# 23005_2.net
KiCad netlist of a schematic drawn in Altium Designer
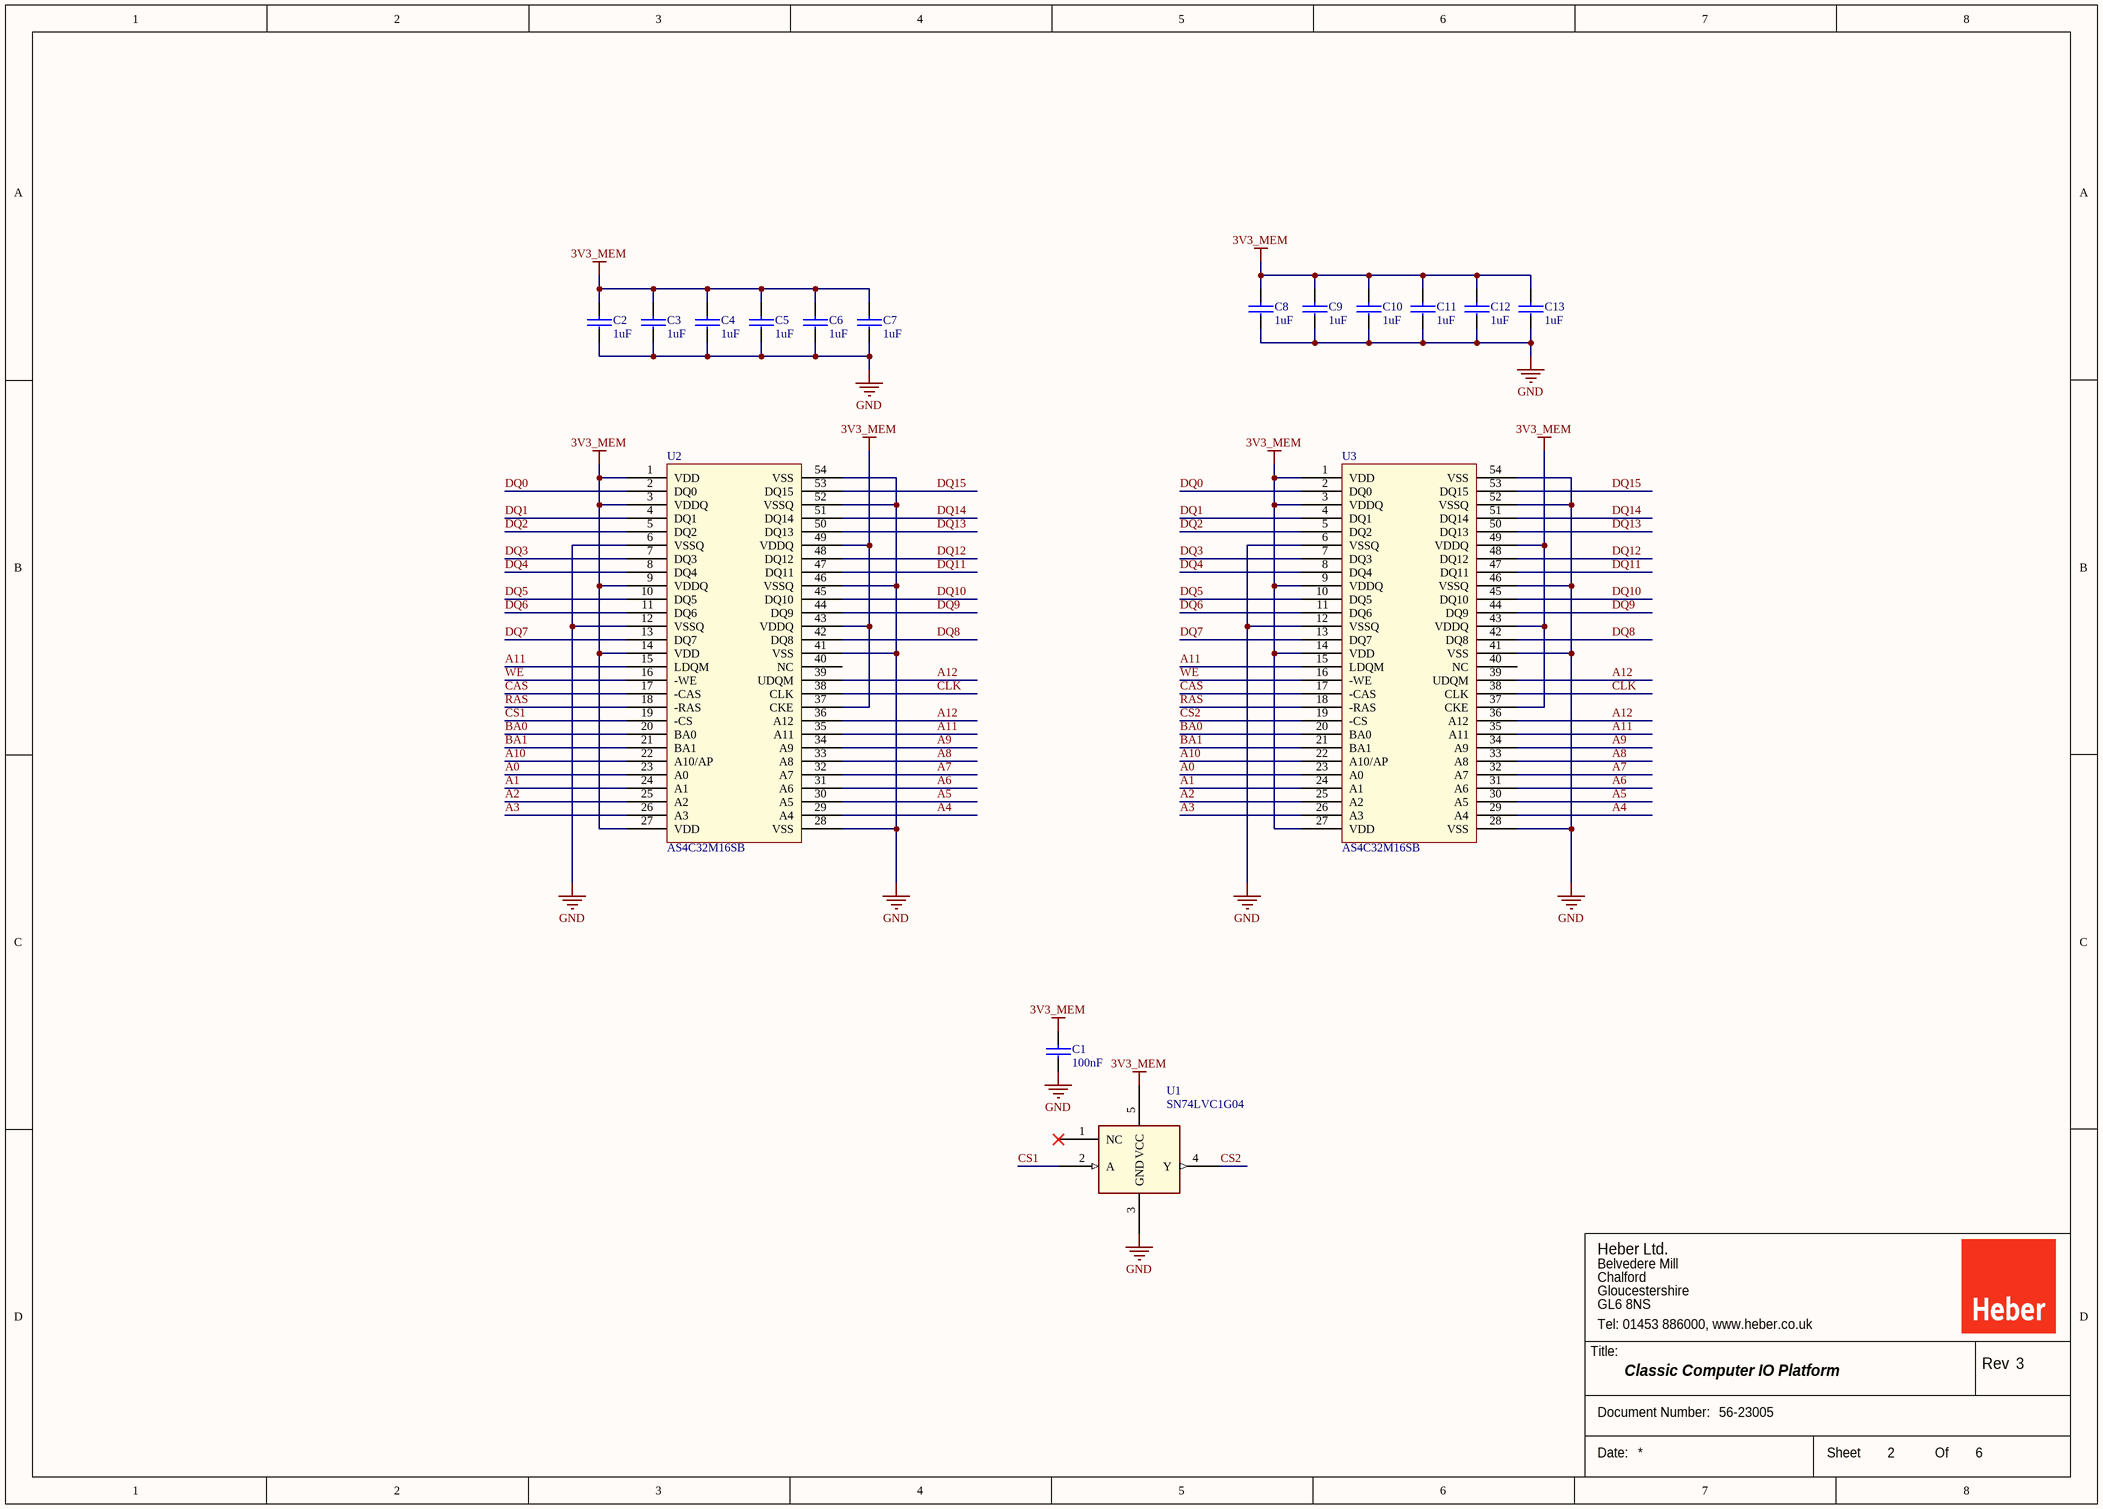
[diagram p0: 23005_2.SchDoc]

(export (version "E")
  (design (tool "Eeschema 10.0.6"))
  (components
    (comp (ref "C1") (value "100nF") (footprint "SM0603") (libsource (lib "LIBRARY1_Library") (part "C")))
    (comp (ref "C2") (value "1uF") (footprint "SM0603") (libsource (lib "LIBRARY1_Library") (part "C")))
    (comp (ref "C3") (value "1uF") (footprint "SM0603") (libsource (lib "LIBRARY1_Library") (part "C")))
    (comp (ref "C4") (value "1uF") (footprint "SM0603") (libsource (lib "LIBRARY1_Library") (part "C")))
    (comp (ref "C5") (value "1uF") (footprint "SM0603") (libsource (lib "LIBRARY1_Library") (part "C")))
    (comp (ref "C6") (value "1uF") (footprint "SM0603") (libsource (lib "LIBRARY1_Library") (part "C")))
    (comp (ref "C7") (value "1uF") (footprint "SM0603") (libsource (lib "LIBRARY1_Library") (part "C")))
    (comp (ref "C8") (value "1uF") (footprint "SM0603") (libsource (lib "LIBRARY1_Library") (part "C")))
    (comp (ref "C9") (value "1uF") (footprint "SM0603") (libsource (lib "LIBRARY1_Library") (part "C")))
    (comp (ref "C10") (value "1uF") (footprint "SM0603") (libsource (lib "LIBRARY1_Library") (part "C")))
    (comp (ref "C11") (value "1uF") (footprint "SM0603") (libsource (lib "LIBRARY1_Library") (part "C")))
    (comp (ref "C12") (value "1uF") (footprint "SM0603") (libsource (lib "LIBRARY1_Library") (part "C")))
    (comp (ref "C13") (value "1uF") (footprint "SM0603") (libsource (lib "LIBRARY1_Library") (part "C")))
    (comp (ref "U1")
      (value "SN74LVC1G04")
      (footprint "SOT23-5")
      (libsource (lib "LIBRARY1_Library") (part "SN74LVC1G07"))
    )
    (comp (ref "U2")
      (value "AS4C32M16SB")
      (footprint "TSOP54/080")
      (libsource (lib "23005") (part "AS4C32M16SB"))
    )
    (comp (ref "U3")
      (value "AS4C32M16SB")
      (footprint "TSOP54/080")
      (libsource (lib "23005") (part "AS4C32M16SB"))
    )
  )
  (nets
    (net (code "1") (name "/A0") (class "Default")
      (node (ref "U2") (pin "23") (pinfunction "A0_23") (pintype "passive"))
      (node (ref "U3") (pin "23") (pinfunction "A0_23") (pintype "passive"))
    )
    (net (code "2") (name "/A1") (class "Default")
      (node (ref "U2") (pin "24") (pinfunction "A1_24") (pintype "passive"))
      (node (ref "U3") (pin "24") (pinfunction "A1_24") (pintype "passive"))
    )
    (net (code "3") (name "/A2") (class "Default")
      (node (ref "U2") (pin "25") (pinfunction "A2_25") (pintype "passive"))
      (node (ref "U3") (pin "25") (pinfunction "A2_25") (pintype "passive"))
    )
    (net (code "4") (name "/A3") (class "Default")
      (node (ref "U2") (pin "26") (pinfunction "A3_26") (pintype "passive"))
      (node (ref "U3") (pin "26") (pinfunction "A3_26") (pintype "passive"))
    )
    (net (code "5") (name "/A4") (class "Default")
      (node (ref "U2") (pin "29") (pinfunction "A4_29") (pintype "passive"))
      (node (ref "U3") (pin "29") (pinfunction "A4_29") (pintype "passive"))
    )
    (net (code "6") (name "/A5") (class "Default")
      (node (ref "U2") (pin "30") (pinfunction "A5_30") (pintype "passive"))
      (node (ref "U3") (pin "30") (pinfunction "A5_30") (pintype "passive"))
    )
    (net (code "7") (name "/A6") (class "Default")
      (node (ref "U2") (pin "31") (pinfunction "A6_31") (pintype "passive"))
      (node (ref "U3") (pin "31") (pinfunction "A6_31") (pintype "passive"))
    )
    (net (code "8") (name "/A7") (class "Default")
      (node (ref "U2") (pin "32") (pinfunction "A7_32") (pintype "passive"))
      (node (ref "U3") (pin "32") (pinfunction "A7_32") (pintype "passive"))
    )
    (net (code "9") (name "/A8") (class "Default")
      (node (ref "U2") (pin "33") (pinfunction "A8_33") (pintype "passive"))
      (node (ref "U3") (pin "33") (pinfunction "A8_33") (pintype "passive"))
    )
    (net (code "10") (name "/A9") (class "Default")
      (node (ref "U2") (pin "34") (pinfunction "A9_34") (pintype "passive"))
      (node (ref "U3") (pin "34") (pinfunction "A9_34") (pintype "passive"))
    )
    (net (code "11") (name "/A10") (class "Default")
      (node (ref "U2") (pin "22") (pinfunction "A10/AP_22") (pintype "passive"))
      (node (ref "U3") (pin "22") (pinfunction "A10/AP_22") (pintype "passive"))
    )
    (net (code "12") (name "/A11") (class "Default")
      (node (ref "U2") (pin "15") (pinfunction "LDQM_15") (pintype "passive"))
      (node (ref "U2") (pin "35") (pinfunction "A11_35") (pintype "passive"))
      (node (ref "U3") (pin "15") (pinfunction "LDQM_15") (pintype "passive"))
      (node (ref "U3") (pin "35") (pinfunction "A11_35") (pintype "passive"))
    )
    (net (code "13") (name "/A12") (class "Default")
      (node (ref "U2") (pin "36") (pinfunction "A12_36") (pintype "passive"))
      (node (ref "U2") (pin "39") (pinfunction "UDQM_39") (pintype "passive"))
      (node (ref "U3") (pin "36") (pinfunction "A12_36") (pintype "passive"))
      (node (ref "U3") (pin "39") (pinfunction "UDQM_39") (pintype "passive"))
    )
    (net (code "14") (name "/BA0") (class "Default")
      (node (ref "U2") (pin "20") (pinfunction "BA0_20") (pintype "passive"))
      (node (ref "U3") (pin "20") (pinfunction "BA0_20") (pintype "passive"))
    )
    (net (code "15") (name "/BA1") (class "Default")
      (node (ref "U2") (pin "21") (pinfunction "BA1_21") (pintype "passive"))
      (node (ref "U3") (pin "21") (pinfunction "BA1_21") (pintype "passive"))
    )
    (net (code "16") (name "/CAS") (class "Default")
      (node (ref "U2") (pin "17") (pinfunction "-CAS_17") (pintype "passive"))
      (node (ref "U3") (pin "17") (pinfunction "-CAS_17") (pintype "passive"))
    )
    (net (code "17") (name "/CLK") (class "Default")
      (node (ref "U2") (pin "38") (pinfunction "CLK_38") (pintype "passive"))
      (node (ref "U3") (pin "38") (pinfunction "CLK_38") (pintype "passive"))
    )
    (net (code "18") (name "/CS1") (class "Default")
      (node (ref "U1") (pin "2") (pinfunction "A_2") (pintype "input"))
      (node (ref "U2") (pin "19") (pinfunction "-CS_19") (pintype "passive"))
    )
    (net (code "19") (name "/CS2") (class "Default")
      (node (ref "U1") (pin "4") (pinfunction "Y_4") (pintype "output"))
      (node (ref "U3") (pin "19") (pinfunction "-CS_19") (pintype "passive"))
    )
    (net (code "20") (name "/DQ0") (class "Default")
      (node (ref "U2") (pin "2") (pinfunction "DQ0_2") (pintype "passive"))
      (node (ref "U3") (pin "2") (pinfunction "DQ0_2") (pintype "passive"))
    )
    (net (code "21") (name "/DQ1") (class "Default")
      (node (ref "U2") (pin "4") (pinfunction "DQ1_4") (pintype "passive"))
      (node (ref "U3") (pin "4") (pinfunction "DQ1_4") (pintype "passive"))
    )
    (net (code "22") (name "/DQ2") (class "Default")
      (node (ref "U2") (pin "5") (pinfunction "DQ2_5") (pintype "passive"))
      (node (ref "U3") (pin "5") (pinfunction "DQ2_5") (pintype "passive"))
    )
    (net (code "23") (name "/DQ3") (class "Default")
      (node (ref "U2") (pin "7") (pinfunction "DQ3_7") (pintype "passive"))
      (node (ref "U3") (pin "7") (pinfunction "DQ3_7") (pintype "passive"))
    )
    (net (code "24") (name "/DQ4") (class "Default")
      (node (ref "U2") (pin "8") (pinfunction "DQ4_8") (pintype "passive"))
      (node (ref "U3") (pin "8") (pinfunction "DQ4_8") (pintype "passive"))
    )
    (net (code "25") (name "/DQ5") (class "Default")
      (node (ref "U2") (pin "10") (pinfunction "DQ5_10") (pintype "passive"))
      (node (ref "U3") (pin "10") (pinfunction "DQ5_10") (pintype "passive"))
    )
    (net (code "26") (name "/DQ6") (class "Default")
      (node (ref "U2") (pin "11") (pinfunction "DQ6_11") (pintype "passive"))
      (node (ref "U3") (pin "11") (pinfunction "DQ6_11") (pintype "passive"))
    )
    (net (code "27") (name "/DQ7") (class "Default")
      (node (ref "U2") (pin "13") (pinfunction "DQ7_13") (pintype "passive"))
      (node (ref "U3") (pin "13") (pinfunction "DQ7_13") (pintype "passive"))
    )
    (net (code "28") (name "/DQ8") (class "Default")
      (node (ref "U2") (pin "42") (pinfunction "DQ8_42") (pintype "passive"))
      (node (ref "U3") (pin "42") (pinfunction "DQ8_42") (pintype "passive"))
    )
    (net (code "29") (name "/DQ9") (class "Default")
      (node (ref "U2") (pin "44") (pinfunction "DQ9_44") (pintype "passive"))
      (node (ref "U3") (pin "44") (pinfunction "DQ9_44") (pintype "passive"))
    )
    (net (code "30") (name "/DQ10") (class "Default")
      (node (ref "U2") (pin "45") (pinfunction "DQ10_45") (pintype "passive"))
      (node (ref "U3") (pin "45") (pinfunction "DQ10_45") (pintype "passive"))
    )
    (net (code "31") (name "/DQ11") (class "Default")
      (node (ref "U2") (pin "47") (pinfunction "DQ11_47") (pintype "passive"))
      (node (ref "U3") (pin "47") (pinfunction "DQ11_47") (pintype "passive"))
    )
    (net (code "32") (name "/DQ12") (class "Default")
      (node (ref "U2") (pin "48") (pinfunction "DQ12_48") (pintype "passive"))
      (node (ref "U3") (pin "48") (pinfunction "DQ12_48") (pintype "passive"))
    )
    (net (code "33") (name "/DQ13") (class "Default")
      (node (ref "U2") (pin "50") (pinfunction "DQ13_50") (pintype "passive"))
      (node (ref "U3") (pin "50") (pinfunction "DQ13_50") (pintype "passive"))
    )
    (net (code "34") (name "/DQ14") (class "Default")
      (node (ref "U2") (pin "51") (pinfunction "DQ14_51") (pintype "passive"))
      (node (ref "U3") (pin "51") (pinfunction "DQ14_51") (pintype "passive"))
    )
    (net (code "35") (name "/DQ15") (class "Default")
      (node (ref "U2") (pin "53") (pinfunction "DQ15_53") (pintype "passive"))
      (node (ref "U3") (pin "53") (pinfunction "DQ15_53") (pintype "passive"))
    )
    (net (code "36") (name "/RAS") (class "Default")
      (node (ref "U2") (pin "18") (pinfunction "-RAS_18") (pintype "passive"))
      (node (ref "U3") (pin "18") (pinfunction "-RAS_18") (pintype "passive"))
    )
    (net (code "37") (name "/WE") (class "Default")
      (node (ref "U2") (pin "16") (pinfunction "-WE_16") (pintype "passive"))
      (node (ref "U3") (pin "16") (pinfunction "-WE_16") (pintype "passive"))
    )
    (net (code "38") (name "3V3_MEM") (class "Default")
      (node (ref "C1") (pin "1") (pinfunction "1_1") (pintype "passive"))
      (node (ref "C10") (pin "1") (pinfunction "1_1") (pintype "passive"))
      (node (ref "C11") (pin "1") (pinfunction "1_1") (pintype "passive"))
      (node (ref "C12") (pin "1") (pinfunction "1_1") (pintype "passive"))
      (node (ref "C13") (pin "1") (pinfunction "1_1") (pintype "passive"))
      (node (ref "C2") (pin "1") (pinfunction "1_1") (pintype "passive"))
      (node (ref "C3") (pin "1") (pinfunction "1_1") (pintype "passive"))
      (node (ref "C4") (pin "1") (pinfunction "1_1") (pintype "passive"))
      (node (ref "C5") (pin "1") (pinfunction "1_1") (pintype "passive"))
      (node (ref "C6") (pin "1") (pinfunction "1_1") (pintype "passive"))
      (node (ref "C7") (pin "1") (pinfunction "1_1") (pintype "passive"))
      (node (ref "C8") (pin "1") (pinfunction "1_1") (pintype "passive"))
      (node (ref "C9") (pin "1") (pinfunction "1_1") (pintype "passive"))
      (node (ref "U1") (pin "5") (pinfunction "VCC_5") (pintype "power_in"))
      (node (ref "U2") (pin "1") (pinfunction "VDD_1") (pintype "passive"))
      (node (ref "U2") (pin "14") (pinfunction "VDD_14") (pintype "passive"))
      (node (ref "U2") (pin "27") (pinfunction "VDD_27") (pintype "passive"))
      (node (ref "U2") (pin "3") (pinfunction "VDDQ_3") (pintype "passive"))
      (node (ref "U2") (pin "37") (pinfunction "CKE_37") (pintype "passive"))
      (node (ref "U2") (pin "43") (pinfunction "VDDQ_43") (pintype "passive"))
      (node (ref "U2") (pin "49") (pinfunction "VDDQ_49") (pintype "passive"))
      (node (ref "U2") (pin "9") (pinfunction "VDDQ_9") (pintype "passive"))
      (node (ref "U3") (pin "1") (pinfunction "VDD_1") (pintype "passive"))
      (node (ref "U3") (pin "14") (pinfunction "VDD_14") (pintype "passive"))
      (node (ref "U3") (pin "27") (pinfunction "VDD_27") (pintype "passive"))
      (node (ref "U3") (pin "3") (pinfunction "VDDQ_3") (pintype "passive"))
      (node (ref "U3") (pin "37") (pinfunction "CKE_37") (pintype "passive"))
      (node (ref "U3") (pin "43") (pinfunction "VDDQ_43") (pintype "passive"))
      (node (ref "U3") (pin "49") (pinfunction "VDDQ_49") (pintype "passive"))
      (node (ref "U3") (pin "9") (pinfunction "VDDQ_9") (pintype "passive"))
    )
    (net (code "39") (name "GND") (class "Default")
      (node (ref "C1") (pin "2") (pinfunction "2_2") (pintype "passive"))
      (node (ref "C10") (pin "2") (pinfunction "2_2") (pintype "passive"))
      (node (ref "C11") (pin "2") (pinfunction "2_2") (pintype "passive"))
      (node (ref "C12") (pin "2") (pinfunction "2_2") (pintype "passive"))
      (node (ref "C13") (pin "2") (pinfunction "2_2") (pintype "passive"))
      (node (ref "C2") (pin "2") (pinfunction "2_2") (pintype "passive"))
      (node (ref "C3") (pin "2") (pinfunction "2_2") (pintype "passive"))
      (node (ref "C4") (pin "2") (pinfunction "2_2") (pintype "passive"))
      (node (ref "C5") (pin "2") (pinfunction "2_2") (pintype "passive"))
      (node (ref "C6") (pin "2") (pinfunction "2_2") (pintype "passive"))
      (node (ref "C7") (pin "2") (pinfunction "2_2") (pintype "passive"))
      (node (ref "C8") (pin "2") (pinfunction "2_2") (pintype "passive"))
      (node (ref "C9") (pin "2") (pinfunction "2_2") (pintype "passive"))
      (node (ref "U1") (pin "3") (pinfunction "GND_3") (pintype "power_in"))
      (node (ref "U2") (pin "12") (pinfunction "VSSQ_12") (pintype "passive"))
      (node (ref "U2") (pin "28") (pinfunction "VSS_28") (pintype "passive"))
      (node (ref "U2") (pin "41") (pinfunction "VSS_41") (pintype "passive"))
      (node (ref "U2") (pin "46") (pinfunction "VSSQ_46") (pintype "passive"))
      (node (ref "U2") (pin "52") (pinfunction "VSSQ_52") (pintype "passive"))
      (node (ref "U2") (pin "54") (pinfunction "VSS_54") (pintype "passive"))
      (node (ref "U2") (pin "6") (pinfunction "VSSQ_6") (pintype "passive"))
      (node (ref "U3") (pin "12") (pinfunction "VSSQ_12") (pintype "passive"))
      (node (ref "U3") (pin "28") (pinfunction "VSS_28") (pintype "passive"))
      (node (ref "U3") (pin "41") (pinfunction "VSS_41") (pintype "passive"))
      (node (ref "U3") (pin "46") (pinfunction "VSSQ_46") (pintype "passive"))
      (node (ref "U3") (pin "52") (pinfunction "VSSQ_52") (pintype "passive"))
      (node (ref "U3") (pin "54") (pinfunction "VSS_54") (pintype "passive"))
      (node (ref "U3") (pin "6") (pinfunction "VSSQ_6") (pintype "passive"))
    )
    (net (code "40") (name "unconnected-(U1-NC-Pad1)") (class "Default")
      (node (ref "U1") (pin "1") (pinfunction "NC_1") (pintype "passive+no_connect"))
    )
    (net (code "41") (name "unconnected-(U2-NC-Pad40)") (class "Default")
      (node (ref "U2") (pin "40") (pinfunction "NC_40") (pintype "passive"))
    )
    (net (code "42") (name "unconnected-(U3-NC-Pad40)") (class "Default")
      (node (ref "U3") (pin "40") (pinfunction "NC_40") (pintype "passive"))
    )
  )
)
